# memoryboard3.net
KiCad netlist of a schematic drawn in EAGLE
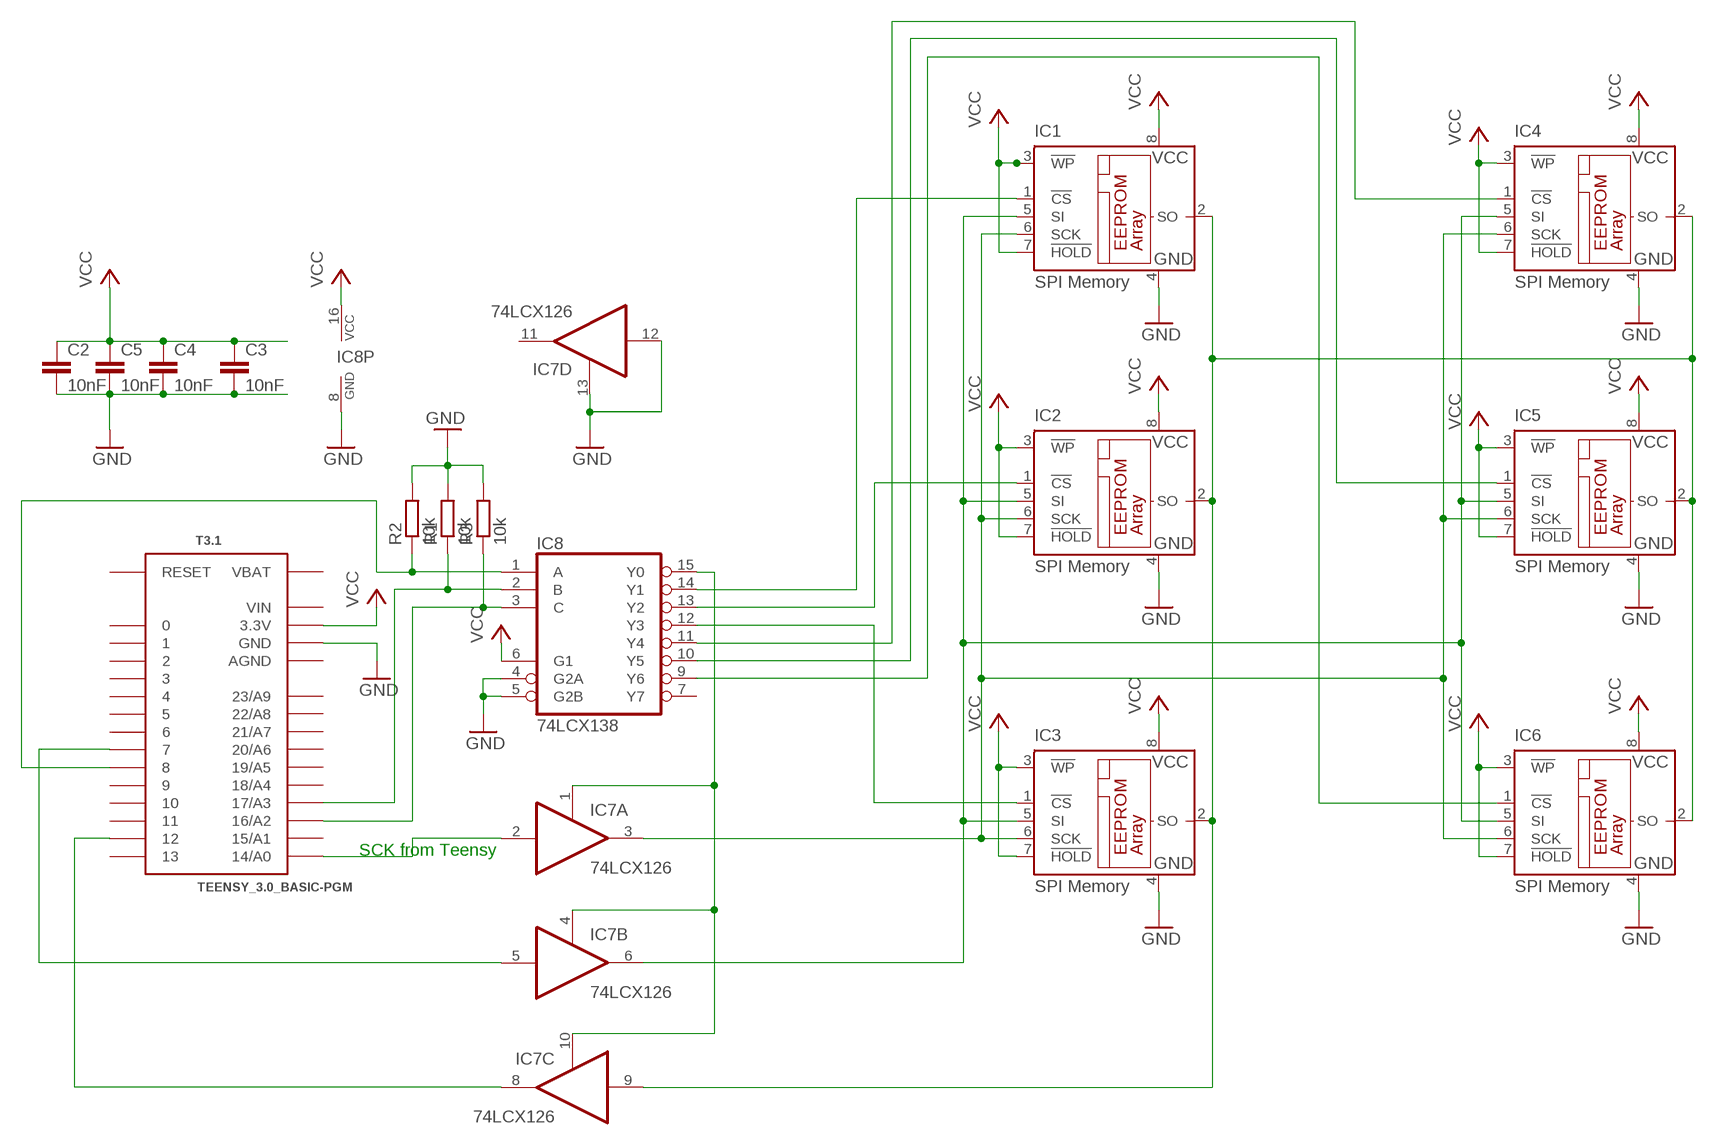
[diagram p0: schematic, sheet 1]

(export (version "E")
  (design (tool "Eeschema 10.0.6"))
  (components
    (comp (ref "C2")
      (value "10nF")
      (footprint "eagle-import:C0603")
      (libsource (lib "eagle-import") (part "C-EUC0603"))
    )
    (comp (ref "C3")
      (value "10nF")
      (footprint "eagle-import:C0603")
      (libsource (lib "eagle-import") (part "C-EUC0603"))
    )
    (comp (ref "C4")
      (value "10nF")
      (footprint "eagle-import:C0603")
      (libsource (lib "eagle-import") (part "C-EUC0603"))
    )
    (comp (ref "C5")
      (value "10nF")
      (footprint "eagle-import:C0603")
      (libsource (lib "eagle-import") (part "C-EUC0603"))
    )
    (comp (ref "IC1")
      (value "SPI Memory")
      (footprint "eagle-import:SO-08")
      (fields (field (name "MF") "MICROCHIP") (field (name "MPN") "25C080/SN"))
      (libsource (lib "eagle-import") (part "25SNC080"))
    )
    (comp (ref "IC2")
      (value "SPI Memory")
      (footprint "eagle-import:SO-08")
      (fields (field (name "MF") "MICROCHIP") (field (name "MPN") "25C080/SN"))
      (libsource (lib "eagle-import") (part "25SNC080"))
    )
    (comp (ref "IC3")
      (value "SPI Memory")
      (footprint "eagle-import:SO-08")
      (fields (field (name "MF") "MICROCHIP") (field (name "MPN") "25C080/SN"))
      (libsource (lib "eagle-import") (part "25SNC080"))
    )
    (comp (ref "IC4")
      (value "SPI Memory")
      (footprint "eagle-import:SO-08")
      (fields (field (name "MF") "MICROCHIP") (field (name "MPN") "25C080/SN"))
      (libsource (lib "eagle-import") (part "25SNC080"))
    )
    (comp (ref "IC5")
      (value "SPI Memory")
      (footprint "eagle-import:SO-08")
      (fields (field (name "MF") "MICROCHIP") (field (name "MPN") "25C080/SN"))
      (libsource (lib "eagle-import") (part "25SNC080"))
    )
    (comp (ref "IC6")
      (value "SPI Memory")
      (footprint "eagle-import:SO-08")
      (fields (field (name "MF") "MICROCHIP") (field (name "MPN") "25C080/SN"))
      (libsource (lib "eagle-import") (part "25SNC080"))
    )
    (comp (ref "IC7")
      (value "74LCX126")
      (footprint "eagle-import:SO14")
      (libsource (lib "eagle-import") (part "74126DAC"))
    )
    (comp (ref "IC8")
      (value "74LCX138")
      (footprint "eagle-import:SO16")
      (libsource (lib "eagle-import") (part "74138DHC"))
    )
    (comp (ref "R1")
      (value "10k")
      (footprint "eagle-import:R0603")
      (libsource (lib "eagle-import") (part "R-EU_R0603"))
    )
    (comp (ref "R2")
      (value "10k")
      (footprint "eagle-import:R0603")
      (libsource (lib "eagle-import") (part "R-EU_R0603"))
    )
    (comp (ref "R3")
      (value "10k")
      (footprint "eagle-import:R0603")
      (libsource (lib "eagle-import") (part "R-EU_R0603"))
    )
    (comp (ref "T3.1")
      (value "TEENSY_3.0_BASIC-PGM")
      (footprint "eagle-import:TEENSY_3.0_BASIC-PGM")
      (libsource (lib "eagle-import") (part "TEENSY_3.0_BASIC-PGM"))
    )
  )
  (nets
    (net (code "1") (name "/AGND") (class "Default")
      (node (ref "T3.1") (pin "AGND") (pinfunction "AGND_AGND") (pintype "power_in"))
    )
    (net (code "2") (name "/VBAT") (class "Default")
      (node (ref "T3.1") (pin "VBAT") (pinfunction "VBAT_VBAT") (pintype "power_in"))
    )
    (net (code "3") (name "/VIN") (class "Default")
      (node (ref "T3.1") (pin "VIN") (pinfunction "VIN_VIN") (pintype "power_in"))
    )
    (net (code "4") (name "GND") (class "Default")
      (node (ref "C2") (pin "2") (pinfunction "2_2") (pintype "passive"))
      (node (ref "C3") (pin "2") (pinfunction "2_2") (pintype "passive"))
      (node (ref "C4") (pin "2") (pinfunction "2_2") (pintype "passive"))
      (node (ref "C5") (pin "2") (pinfunction "2_2") (pintype "passive"))
      (node (ref "IC1") (pin "4") (pinfunction "GND_4") (pintype "power_in"))
      (node (ref "IC2") (pin "4") (pinfunction "GND_4") (pintype "power_in"))
      (node (ref "IC3") (pin "4") (pinfunction "GND_4") (pintype "power_in"))
      (node (ref "IC4") (pin "4") (pinfunction "GND_4") (pintype "power_in"))
      (node (ref "IC5") (pin "4") (pinfunction "GND_4") (pintype "power_in"))
      (node (ref "IC6") (pin "4") (pinfunction "GND_4") (pintype "power_in"))
      (node (ref "IC7") (pin "12") (pinfunction "I_12") (pintype "input"))
      (node (ref "IC7") (pin "13") (pinfunction "OE_13") (pintype "input"))
      (node (ref "IC8") (pin "4") (pinfunction "G2A_4") (pintype "input"))
      (node (ref "IC8") (pin "5") (pinfunction "G2B_5") (pintype "input"))
      (node (ref "IC8") (pin "8") (pinfunction "GND_8") (pintype "power_in"))
      (node (ref "R1") (pin "2") (pinfunction "2_2") (pintype "passive"))
      (node (ref "R2") (pin "2") (pinfunction "2_2") (pintype "passive"))
      (node (ref "R3") (pin "2") (pinfunction "2_2") (pintype "passive"))
      (node (ref "T3.1") (pin "GND") (pinfunction "GND_GND") (pintype "power_in"))
      (node (ref "T3.1") (pin "GND1") (pinfunction "GND_GND1") (pintype "power_in"))
    )
    (net (code "5") (name "Net-(IC1-SCK)") (class "Default")
      (node (ref "IC1") (pin "6") (pinfunction "SCK_6") (pintype "input"))
      (node (ref "IC2") (pin "6") (pinfunction "SCK_6") (pintype "input"))
      (node (ref "IC3") (pin "6") (pinfunction "SCK_6") (pintype "input"))
      (node (ref "IC4") (pin "6") (pinfunction "SCK_6") (pintype "input"))
      (node (ref "IC5") (pin "6") (pinfunction "SCK_6") (pintype "input"))
      (node (ref "IC6") (pin "6") (pinfunction "SCK_6") (pintype "input"))
      (node (ref "IC7") (pin "3") (pinfunction "O_3") (pintype "output"))
    )
    (net (code "6") (name "Net-(IC1-SI)") (class "Default")
      (node (ref "IC1") (pin "5") (pinfunction "SI_5") (pintype "input"))
      (node (ref "IC2") (pin "5") (pinfunction "SI_5") (pintype "input"))
      (node (ref "IC3") (pin "5") (pinfunction "SI_5") (pintype "input"))
      (node (ref "IC4") (pin "5") (pinfunction "SI_5") (pintype "input"))
      (node (ref "IC5") (pin "5") (pinfunction "SI_5") (pintype "input"))
      (node (ref "IC6") (pin "5") (pinfunction "SI_5") (pintype "input"))
      (node (ref "IC7") (pin "6") (pinfunction "O_6") (pintype "output"))
    )
    (net (code "7") (name "Net-(IC1-SO)") (class "Default")
      (node (ref "IC1") (pin "2") (pinfunction "SO_2") (pintype "bidirectional"))
      (node (ref "IC2") (pin "2") (pinfunction "SO_2") (pintype "bidirectional"))
      (node (ref "IC3") (pin "2") (pinfunction "SO_2") (pintype "bidirectional"))
      (node (ref "IC4") (pin "2") (pinfunction "SO_2") (pintype "bidirectional"))
      (node (ref "IC5") (pin "2") (pinfunction "SO_2") (pintype "bidirectional"))
      (node (ref "IC6") (pin "2") (pinfunction "SO_2") (pintype "bidirectional"))
      (node (ref "IC7") (pin "9") (pinfunction "I_9") (pintype "input"))
    )
    (net (code "8") (name "Net-(IC1-~{CS})") (class "Default")
      (node (ref "IC1") (pin "1") (pinfunction "~{CS}_1") (pintype "input"))
      (node (ref "IC8") (pin "14") (pinfunction "Y1_14") (pintype "output"))
    )
    (net (code "9") (name "Net-(IC2-~{CS})") (class "Default")
      (node (ref "IC2") (pin "1") (pinfunction "~{CS}_1") (pintype "input"))
      (node (ref "IC8") (pin "13") (pinfunction "Y2_13") (pintype "output"))
    )
    (net (code "10") (name "Net-(IC3-~{CS})") (class "Default")
      (node (ref "IC3") (pin "1") (pinfunction "~{CS}_1") (pintype "input"))
      (node (ref "IC8") (pin "12") (pinfunction "Y3_12") (pintype "output"))
    )
    (net (code "11") (name "Net-(IC4-~{CS})") (class "Default")
      (node (ref "IC4") (pin "1") (pinfunction "~{CS}_1") (pintype "input"))
      (node (ref "IC8") (pin "11") (pinfunction "Y4_11") (pintype "output"))
    )
    (net (code "12") (name "Net-(IC5-~{CS})") (class "Default")
      (node (ref "IC5") (pin "1") (pinfunction "~{CS}_1") (pintype "input"))
      (node (ref "IC8") (pin "10") (pinfunction "Y5_10") (pintype "output"))
    )
    (net (code "13") (name "Net-(IC6-~{CS})") (class "Default")
      (node (ref "IC6") (pin "1") (pinfunction "~{CS}_1") (pintype "input"))
      (node (ref "IC8") (pin "9") (pinfunction "Y6_9") (pintype "output"))
    )
    (net (code "14") (name "Net-(IC7A-I)") (class "Default")
      (node (ref "IC7") (pin "2") (pinfunction "I_2") (pintype "input"))
      (node (ref "T3.1") (pin "14/A0") (pinfunction "14/A0_14/A0") (pintype "bidirectional"))
    )
    (net (code "15") (name "Net-(IC7A-OE)") (class "Default")
      (node (ref "IC7") (pin "1") (pinfunction "OE_1") (pintype "input"))
      (node (ref "IC7") (pin "10") (pinfunction "OE_10") (pintype "input"))
      (node (ref "IC7") (pin "4") (pinfunction "OE_4") (pintype "input"))
      (node (ref "IC8") (pin "15") (pinfunction "Y0_15") (pintype "output"))
    )
    (net (code "16") (name "Net-(IC7B-I)") (class "Default")
      (node (ref "IC7") (pin "5") (pinfunction "I_5") (pintype "input"))
      (node (ref "T3.1") (pin "7") (pinfunction "7_7") (pintype "bidirectional"))
    )
    (net (code "17") (name "Net-(IC7C-O)") (class "Default")
      (node (ref "IC7") (pin "8") (pinfunction "O_8") (pintype "output"))
      (node (ref "T3.1") (pin "12") (pinfunction "12_12") (pintype "bidirectional"))
    )
    (net (code "18") (name "Net-(IC8A-A)") (class "Default")
      (node (ref "IC8") (pin "1") (pinfunction "A_1") (pintype "input"))
      (node (ref "R2") (pin "1") (pinfunction "1_1") (pintype "passive"))
      (node (ref "T3.1") (pin "8") (pinfunction "8_8") (pintype "bidirectional"))
    )
    (net (code "19") (name "Net-(IC8A-B)") (class "Default")
      (node (ref "IC8") (pin "2") (pinfunction "B_2") (pintype "input"))
      (node (ref "R1") (pin "1") (pinfunction "1_1") (pintype "passive"))
      (node (ref "T3.1") (pin "17/A3") (pinfunction "17/A3_17/A3") (pintype "bidirectional"))
    )
    (net (code "20") (name "Net-(IC8A-C)") (class "Default")
      (node (ref "IC8") (pin "3") (pinfunction "C_3") (pintype "input"))
      (node (ref "R3") (pin "1") (pinfunction "1_1") (pintype "passive"))
      (node (ref "T3.1") (pin "16/A2") (pinfunction "16/A2_16/A2") (pintype "bidirectional"))
    )
    (net (code "21") (name "VCC") (class "Default")
      (node (ref "C2") (pin "1") (pinfunction "1_1") (pintype "passive"))
      (node (ref "C3") (pin "1") (pinfunction "1_1") (pintype "passive"))
      (node (ref "C4") (pin "1") (pinfunction "1_1") (pintype "passive"))
      (node (ref "C5") (pin "1") (pinfunction "1_1") (pintype "passive"))
      (node (ref "IC1") (pin "3") (pinfunction "~{WP}_3") (pintype "input"))
      (node (ref "IC1") (pin "7") (pinfunction "~{HOLD}_7") (pintype "input"))
      (node (ref "IC1") (pin "8") (pinfunction "VCC_8") (pintype "power_in"))
      (node (ref "IC2") (pin "3") (pinfunction "~{WP}_3") (pintype "input"))
      (node (ref "IC2") (pin "7") (pinfunction "~{HOLD}_7") (pintype "input"))
      (node (ref "IC2") (pin "8") (pinfunction "VCC_8") (pintype "power_in"))
      (node (ref "IC3") (pin "3") (pinfunction "~{WP}_3") (pintype "input"))
      (node (ref "IC3") (pin "7") (pinfunction "~{HOLD}_7") (pintype "input"))
      (node (ref "IC3") (pin "8") (pinfunction "VCC_8") (pintype "power_in"))
      (node (ref "IC4") (pin "3") (pinfunction "~{WP}_3") (pintype "input"))
      (node (ref "IC4") (pin "7") (pinfunction "~{HOLD}_7") (pintype "input"))
      (node (ref "IC4") (pin "8") (pinfunction "VCC_8") (pintype "power_in"))
      (node (ref "IC5") (pin "3") (pinfunction "~{WP}_3") (pintype "input"))
      (node (ref "IC5") (pin "7") (pinfunction "~{HOLD}_7") (pintype "input"))
      (node (ref "IC5") (pin "8") (pinfunction "VCC_8") (pintype "power_in"))
      (node (ref "IC6") (pin "3") (pinfunction "~{WP}_3") (pintype "input"))
      (node (ref "IC6") (pin "7") (pinfunction "~{HOLD}_7") (pintype "input"))
      (node (ref "IC6") (pin "8") (pinfunction "VCC_8") (pintype "power_in"))
      (node (ref "IC8") (pin "16") (pinfunction "VCC_16") (pintype "power_in"))
      (node (ref "IC8") (pin "6") (pinfunction "G1_6") (pintype "input"))
      (node (ref "T3.1") (pin "3.3V") (pinfunction "3.3V_3.3V") (pintype "power_in"))
      (node (ref "T3.1") (pin "3.3V1") (pinfunction "3.3V_3.3V1") (pintype "power_in"))
    )
    (net (code "22") (name "unconnected-(IC7D-O-Pad11)") (class "Default")
      (node (ref "IC7") (pin "11") (pinfunction "O_11") (pintype "output"))
    )
    (net (code "23") (name "unconnected-(IC8A-Y7-Pad7)") (class "Default")
      (node (ref "IC8") (pin "7") (pinfunction "Y7_7") (pintype "output"))
    )
    (net (code "24") (name "unconnected-(T3.1-Pad0)") (class "Default")
      (node (ref "T3.1") (pin "0") (pinfunction "0_0") (pintype "bidirectional"))
    )
    (net (code "25") (name "unconnected-(T3.1-Pad1)") (class "Default")
      (node (ref "T3.1") (pin "1") (pinfunction "1_1") (pintype "bidirectional"))
    )
    (net (code "26") (name "unconnected-(T3.1-Pad2)") (class "Default")
      (node (ref "T3.1") (pin "2") (pinfunction "2_2") (pintype "bidirectional"))
    )
    (net (code "27") (name "unconnected-(T3.1-Pad3)") (class "Default")
      (node (ref "T3.1") (pin "3") (pinfunction "3_3") (pintype "bidirectional"))
    )
    (net (code "28") (name "unconnected-(T3.1-Pad4)") (class "Default")
      (node (ref "T3.1") (pin "4") (pinfunction "4_4") (pintype "bidirectional"))
    )
    (net (code "29") (name "unconnected-(T3.1-Pad5)") (class "Default")
      (node (ref "T3.1") (pin "5") (pinfunction "5_5") (pintype "bidirectional"))
    )
    (net (code "30") (name "unconnected-(T3.1-Pad6)") (class "Default")
      (node (ref "T3.1") (pin "6") (pinfunction "6_6") (pintype "bidirectional"))
    )
    (net (code "31") (name "unconnected-(T3.1-Pad9)") (class "Default")
      (node (ref "T3.1") (pin "9") (pinfunction "9_9") (pintype "bidirectional"))
    )
    (net (code "32") (name "unconnected-(T3.1-Pad10)") (class "Default")
      (node (ref "T3.1") (pin "10") (pinfunction "10_10") (pintype "bidirectional"))
    )
    (net (code "33") (name "unconnected-(T3.1-Pad11)") (class "Default")
      (node (ref "T3.1") (pin "11") (pinfunction "11_11") (pintype "bidirectional"))
    )
    (net (code "34") (name "unconnected-(T3.1-Pad13)") (class "Default")
      (node (ref "T3.1") (pin "13") (pinfunction "13_13") (pintype "bidirectional"))
    )
    (net (code "35") (name "unconnected-(T3.1-Pad15{slash}A1)") (class "Default")
      (node (ref "T3.1") (pin "15/A1") (pinfunction "15/A1_15/A1") (pintype "bidirectional"))
    )
    (net (code "36") (name "unconnected-(T3.1-Pad18{slash}A4)") (class "Default")
      (node (ref "T3.1") (pin "18/A4") (pinfunction "18/A4_18/A4") (pintype "bidirectional"))
    )
    (net (code "37") (name "unconnected-(T3.1-Pad19{slash}A5)") (class "Default")
      (node (ref "T3.1") (pin "19/A5") (pinfunction "19/A5_19/A5") (pintype "bidirectional"))
    )
    (net (code "38") (name "unconnected-(T3.1-Pad20{slash}A6)") (class "Default")
      (node (ref "T3.1") (pin "20/A6") (pinfunction "20/A6_20/A6") (pintype "bidirectional"))
    )
    (net (code "39") (name "unconnected-(T3.1-Pad21{slash}A7)") (class "Default")
      (node (ref "T3.1") (pin "21/A7") (pinfunction "21/A7_21/A7") (pintype "bidirectional"))
    )
    (net (code "40") (name "unconnected-(T3.1-Pad22{slash}A8)") (class "Default")
      (node (ref "T3.1") (pin "22/A8") (pinfunction "22/A8_22/A8") (pintype "bidirectional"))
    )
    (net (code "41") (name "unconnected-(T3.1-Pad23{slash}A9)") (class "Default")
      (node (ref "T3.1") (pin "23/A9") (pinfunction "23/A9_23/A9") (pintype "bidirectional"))
    )
    (net (code "42") (name "unconnected-(T3.1-PadRESET)") (class "Default")
      (node (ref "T3.1") (pin "RESET") (pinfunction "RESET_RESET") (pintype "bidirectional"))
    )
  )
)
